# XL4432-SMT.net
KiCad netlist of a schematic drawn in EAGLE
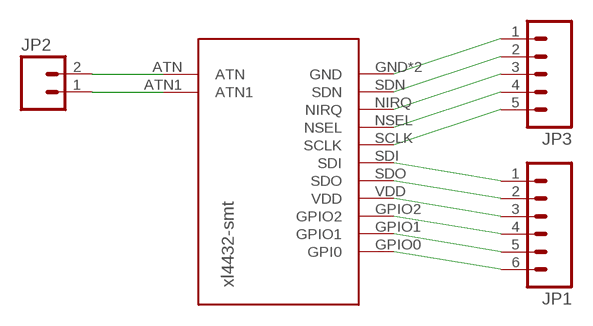
[diagram p0: schematic, sheet 1]

(export (version "E")
  (design (tool "Eeschema 10.0.6"))
  (components
    (comp (ref "JP1")
      (value "M06LOCK")
      (footprint "eagle-import:1X06_LOCK")
      (libsource (lib "eagle-import") (part "M06LOCK"))
    )
    (comp (ref "JP2")
      (value "M02LOCK")
      (footprint "eagle-import:1X02_LOCK")
      (libsource (lib "eagle-import") (part "M02LOCK"))
    )
    (comp (ref "JP3")
      (value "M05LOCK")
      (footprint "eagle-import:1X05_LOCK")
      (libsource (lib "eagle-import") (part "M05LOCK"))
    )
    (comp (ref "U$1")
      (value "XL4432-SMT")
      (footprint "eagle-import:XL4432-SMT")
      (libsource (lib "eagle-import") (part "XL4432-SMT"))
    )
  )
  (nets
    (net (code "1") (name "Net-(JP1-Pad1)") (class "Default")
      (node (ref "JP1") (pin "1") (pinfunction "1_1") (pintype "passive"))
      (node (ref "U$1") (pin "SDI") (pinfunction "SDI_SDI") (pintype "bidirectional"))
    )
    (net (code "2") (name "Net-(JP1-Pad2)") (class "Default")
      (node (ref "JP1") (pin "2") (pinfunction "2_2") (pintype "passive"))
      (node (ref "U$1") (pin "SDO") (pinfunction "SDO_SDO") (pintype "bidirectional"))
    )
    (net (code "3") (name "Net-(JP1-Pad3)") (class "Default")
      (node (ref "JP1") (pin "3") (pinfunction "3_3") (pintype "passive"))
      (node (ref "U$1") (pin "VDD") (pinfunction "VDD_VDD") (pintype "bidirectional"))
    )
    (net (code "4") (name "Net-(JP1-Pad4)") (class "Default")
      (node (ref "JP1") (pin "4") (pinfunction "4_4") (pintype "passive"))
      (node (ref "U$1") (pin "GPIO2") (pinfunction "GPIO2_GPIO2") (pintype "bidirectional"))
    )
    (net (code "5") (name "Net-(JP1-Pad5)") (class "Default")
      (node (ref "JP1") (pin "5") (pinfunction "5_5") (pintype "passive"))
      (node (ref "U$1") (pin "GPIO1") (pinfunction "GPIO1_GPIO1") (pintype "bidirectional"))
    )
    (net (code "6") (name "Net-(JP2-Pad1)") (class "Default")
      (node (ref "JP2") (pin "1") (pinfunction "1_1") (pintype "passive"))
      (node (ref "U$1") (pin "ATN1") (pinfunction "ATN1_ATN1") (pintype "bidirectional"))
    )
    (net (code "7") (name "Net-(JP2-Pad2)") (class "Default")
      (node (ref "JP2") (pin "2") (pinfunction "2_2") (pintype "passive"))
      (node (ref "U$1") (pin "ATN") (pinfunction "ATN_ATN") (pintype "bidirectional"))
    )
    (net (code "8") (name "Net-(JP3-Pad1)") (class "Default")
      (node (ref "JP3") (pin "1") (pinfunction "1_1") (pintype "passive"))
      (node (ref "U$1") (pin "GND") (pinfunction "GND_GND") (pintype "bidirectional"))
      (node (ref "U$1") (pin "GND1") (pinfunction "GND_GND1") (pintype "bidirectional"))
    )
    (net (code "9") (name "Net-(JP3-Pad2)") (class "Default")
      (node (ref "JP3") (pin "2") (pinfunction "2_2") (pintype "passive"))
      (node (ref "U$1") (pin "SDN") (pinfunction "SDN_SDN") (pintype "bidirectional"))
    )
    (net (code "10") (name "Net-(JP3-Pad3)") (class "Default")
      (node (ref "JP3") (pin "3") (pinfunction "3_3") (pintype "passive"))
      (node (ref "U$1") (pin "NIRQ") (pinfunction "NIRQ_NIRQ") (pintype "bidirectional"))
    )
    (net (code "11") (name "Net-(JP3-Pad4)") (class "Default")
      (node (ref "JP3") (pin "4") (pinfunction "4_4") (pintype "passive"))
      (node (ref "U$1") (pin "NSEL") (pinfunction "NSEL_NSEL") (pintype "bidirectional"))
    )
    (net (code "12") (name "Net-(JP3-Pad5)") (class "Default")
      (node (ref "JP3") (pin "5") (pinfunction "5_5") (pintype "passive"))
      (node (ref "U$1") (pin "SCLK") (pinfunction "SCLK_SCLK") (pintype "bidirectional"))
    )
    (net (code "13") (name "Net-(U$1-GPI0)") (class "Default")
      (node (ref "JP1") (pin "6") (pinfunction "6_6") (pintype "passive"))
      (node (ref "U$1") (pin "GPIO0") (pinfunction "GPI0_GPIO0") (pintype "bidirectional"))
    )
  )
)
